# SetResetIC.net
KiCad netlist of a schematic drawn in Altium Designer
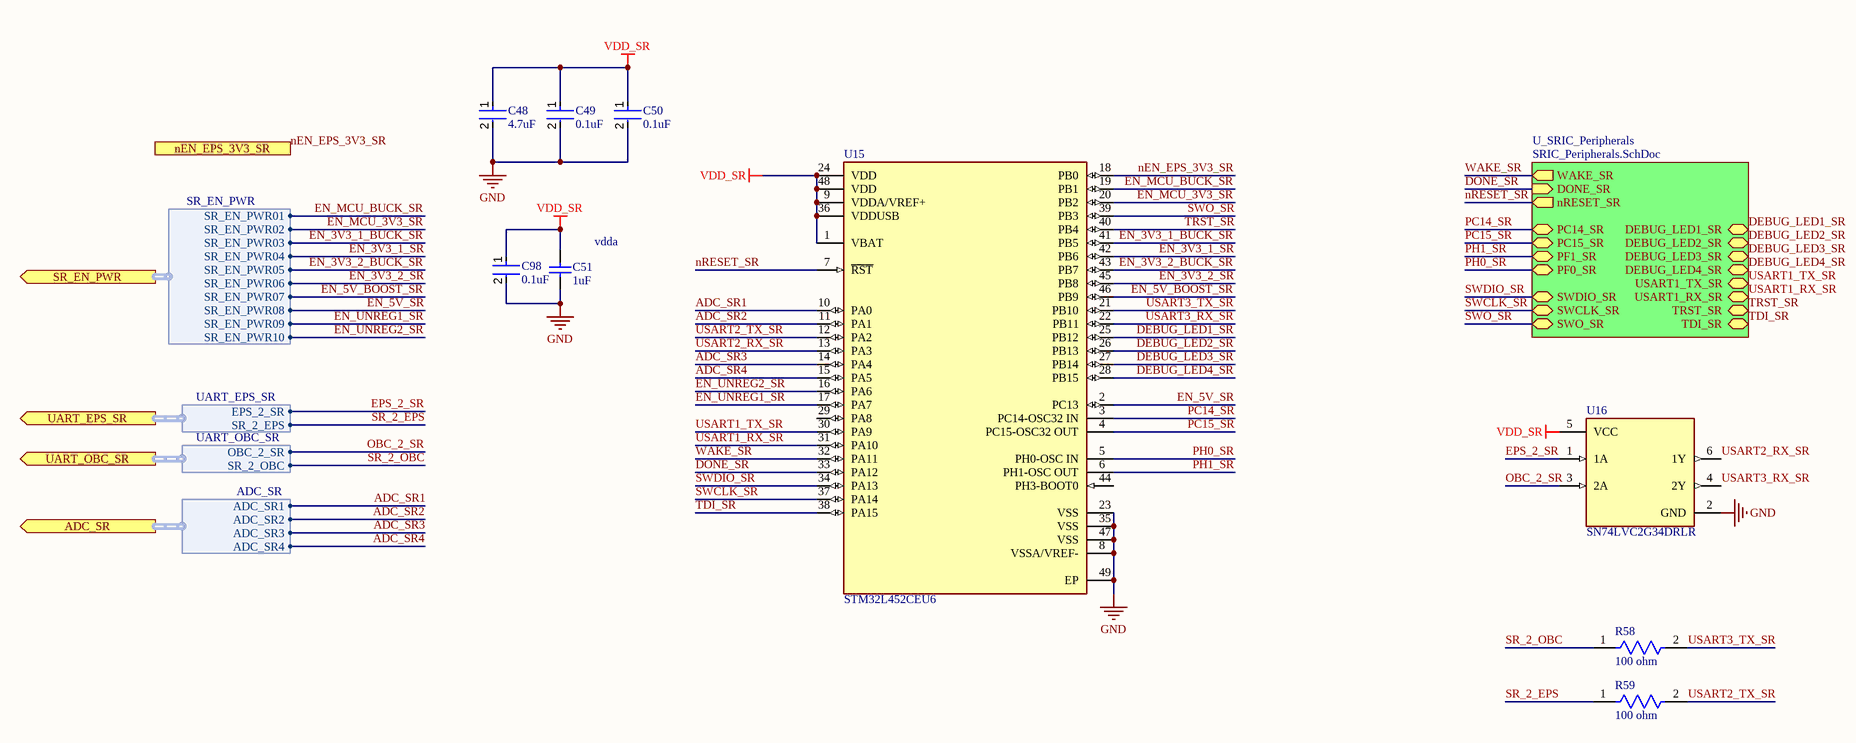
[diagram p0: SetResetIC.SchDoc]

(export (version "E")
  (design (tool "Eeschema 10.0.6"))
  (components
    (comp (ref "C48")
      (value "4.7uF")
      (footprint "FP-GRM188-0_15-IPC_A")
      (description "CAP CER 4.7UF 10V X7S 0603")
      (fields (field (name "TOLERANCE") "10%"))
      (libsource (lib "Altium Content Vault") (part "02cd4be3c70576c341d710602a673aa"))
    )
    (comp (ref "C49")
      (value "0.1uF")
      (footprint "FP-C0603C-CF-MFG")
      (description "CAP CER 0.1UF 50V X7R 0603")
      (fields (field (name "TOLERANCE") "0.1") (field (name "MANUFACTURER") "KEMET"))
      (libsource (lib "Altium Content Vault") (part "b4654b650e69147ec39a6b967a45e02"))
    )
    (comp (ref "C50")
      (value "0.1uF")
      (footprint "FP-C0603C-CF-MFG")
      (description "CAP CER 0.1UF 50V X7R 0603")
      (fields (field (name "TOLERANCE") "0.1") (field (name "MANUFACTURER") "KEMET"))
      (libsource (lib "Altium Content Vault") (part "b4654b650e69147ec39a6b967a45e02"))
    )
    (comp (ref "C51")
      (value "1uF")
      (footprint "CAPC1608X90X35ML10T15")
      (fields (field (name "PART NUMBER") "GRM188R71C105KA12J") (field (name "MANUFACTURER") "Murata"))
      (libsource (lib "Altium Content Vault") (part "CAP"))
    )
    (comp (ref "C98")
      (value "0.1uF")
      (footprint "FP-C0603C-CF-MFG")
      (description "CAP CER 0.1UF 50V X7R 0603")
      (fields (field (name "TOLERANCE") "0.1") (field (name "MANUFACTURER") "KEMET"))
      (libsource (lib "Altium Content Vault") (part "b4654b650e69147ec39a6b967a45e02"))
    )
    (comp (ref "R58")
      (value "100 ohm")
      (footprint "FP-ERJP03-MFG")
      (description "ERJ-P03F1000V SMD Chip Resistor, 100 Ohm, ± 1%, 200 mW, 0603 [1608 Metric], Thick Film, Anti-Surge")
      (fields (field (name "TOLERANCE") "1%"))
      (libsource (lib "Altium Content Vault") (part "1029c3af85768c4190bb7ad29bc67b5"))
    )
    (comp (ref "R59")
      (value "100 ohm")
      (footprint "FP-ERJP03-MFG")
      (description "ERJ-P03F1000V SMD Chip Resistor, 100 Ohm, ± 1%, 200 mW, 0603 [1608 Metric], Thick Film, Anti-Surge")
      (fields (field (name "TOLERANCE") "1%"))
      (libsource (lib "Altium Content Vault") (part "1029c3af85768c4190bb7ad29bc67b5"))
    )
    (comp (ref "U15")
      (value "STM32L452CEU6")
      (footprint "FP-UFQFPN48-A0B9-MFG")
      (description "IC MCU 32BIT 512KB FLASH 48QFPN")
      (libsource (lib "Altium Content Vault") (part "a3bdcff68b454379d220d048bba18d7"))
    )
    (comp (ref "U16")
      (value "SN74LVC2G34DRLR")
      (footprint "FP-DRL0006A-MFG")
      (description "IC BUFFER NON-INVERT 5.5V 6SOT")
      (libsource (lib "Altium Content Vault") (part "59303bce76f5fafbc101ba271662c75"))
    )
  )
  (nets
    (net (code "5") (name "/ADC_SR1") (class "Default")
      (node (ref "U15") (pin "10") (pinfunction "PA0_10") (pintype "bidirectional"))
    )
    (net (code "6") (name "/ADC_SR2") (class "Default")
      (node (ref "U15") (pin "11") (pinfunction "PA1_11") (pintype "bidirectional"))
    )
    (net (code "7") (name "/ADC_SR3") (class "Default")
      (node (ref "U15") (pin "14") (pinfunction "PA4_14") (pintype "bidirectional"))
    )
    (net (code "8") (name "/ADC_SR4") (class "Default")
      (node (ref "U15") (pin "15") (pinfunction "PA5_15") (pintype "bidirectional"))
    )
    (net (code "9") (name "/DEBUG_LED1_SR") (class "Default")
      (node (ref "U15") (pin "25") (pinfunction "PB12_25") (pintype "bidirectional"))
    )
    (net (code "10") (name "/DEBUG_LED2_SR") (class "Default")
      (node (ref "U15") (pin "26") (pinfunction "PB13_26") (pintype "bidirectional"))
    )
    (net (code "11") (name "/DEBUG_LED3_SR") (class "Default")
      (node (ref "U15") (pin "27") (pinfunction "PB14_27") (pintype "bidirectional"))
    )
    (net (code "12") (name "/DEBUG_LED4_SR") (class "Default")
      (node (ref "U15") (pin "28") (pinfunction "PB15_28") (pintype "bidirectional"))
    )
    (net (code "13") (name "/DONE_SR") (class "Default")
      (node (ref "U15") (pin "33") (pinfunction "PA12_33") (pintype "bidirectional"))
    )
    (net (code "14") (name "/EN_3V3_1_BUCK_SR") (class "Default")
      (node (ref "U15") (pin "41") (pinfunction "PB5_41") (pintype "bidirectional"))
    )
    (net (code "15") (name "/EN_3V3_1_SR") (class "Default")
      (node (ref "U15") (pin "42") (pinfunction "PB6_42") (pintype "bidirectional"))
    )
    (net (code "16") (name "/EN_3V3_2_BUCK_SR") (class "Default")
      (node (ref "U15") (pin "43") (pinfunction "PB7_43") (pintype "bidirectional"))
    )
    (net (code "17") (name "/EN_3V3_2_SR") (class "Default")
      (node (ref "U15") (pin "45") (pinfunction "PB8_45") (pintype "bidirectional"))
    )
    (net (code "18") (name "/EN_5V_BOOST_SR") (class "Default")
      (node (ref "U15") (pin "46") (pinfunction "PB9_46") (pintype "bidirectional"))
    )
    (net (code "19") (name "/EN_5V_SR") (class "Default")
      (node (ref "U15") (pin "2") (pinfunction "PC13_2") (pintype "bidirectional"))
    )
    (net (code "20") (name "/EN_MCU_3V3_SR") (class "Default")
      (node (ref "U15") (pin "20") (pinfunction "PB2_20") (pintype "bidirectional"))
    )
    (net (code "21") (name "/EN_MCU_BUCK_SR") (class "Default")
      (node (ref "U15") (pin "19") (pinfunction "PB1_19") (pintype "bidirectional"))
    )
    (net (code "22") (name "/EN_UNREG1_SR") (class "Default")
      (node (ref "U15") (pin "17") (pinfunction "PA7_17") (pintype "bidirectional"))
    )
    (net (code "23") (name "/EN_UNREG2_SR") (class "Default")
      (node (ref "U15") (pin "16") (pinfunction "PA6_16") (pintype "bidirectional"))
    )
    (net (code "24") (name "/EPS_2_SR") (class "Default")
      (node (ref "U16") (pin "1") (pinfunction "1A_1") (pintype "input"))
    )
    (net (code "25") (name "/OBC_2_SR") (class "Default")
      (node (ref "U16") (pin "3") (pinfunction "2A_3") (pintype "input"))
    )
    (net (code "26") (name "/PC14_SR") (class "Default")
      (node (ref "U15") (pin "3") (pinfunction "PC14-OSC32_IN_3") (pintype "passive"))
    )
    (net (code "27") (name "/PC15_SR") (class "Default")
      (node (ref "U15") (pin "4") (pinfunction "PC15-OSC32_OUT_4") (pintype "passive"))
    )
    (net (code "28") (name "/PH0_SR") (class "Default")
      (node (ref "U15") (pin "5") (pinfunction "PH0-OSC_IN_5") (pintype "passive"))
    )
    (net (code "29") (name "/PH1_SR") (class "Default")
      (node (ref "U15") (pin "6") (pinfunction "PH1-OSC_OUT_6") (pintype "passive"))
    )
    (net (code "30") (name "/SR_2_EPS") (class "Default")
      (node (ref "R59") (pin "1") (pinfunction "1_1") (pintype "passive"))
    )
    (net (code "31") (name "/SR_2_OBC") (class "Default")
      (node (ref "R58") (pin "1") (pinfunction "1_1") (pintype "passive"))
    )
    (net (code "32") (name "/SWCLK_SR") (class "Default")
      (node (ref "U15") (pin "37") (pinfunction "PA14_37") (pintype "bidirectional"))
    )
    (net (code "33") (name "/SWDIO_SR") (class "Default")
      (node (ref "U15") (pin "34") (pinfunction "PA13_34") (pintype "bidirectional"))
    )
    (net (code "34") (name "/SWO_SR") (class "Default")
      (node (ref "U15") (pin "39") (pinfunction "PB3_39") (pintype "bidirectional"))
    )
    (net (code "35") (name "/TDI_SR") (class "Default")
      (node (ref "U15") (pin "38") (pinfunction "PA15_38") (pintype "bidirectional"))
    )
    (net (code "36") (name "/TRST_SR") (class "Default")
      (node (ref "U15") (pin "40") (pinfunction "PB4_40") (pintype "bidirectional"))
    )
    (net (code "37") (name "/USART1_RX_SR") (class "Default")
      (node (ref "U15") (pin "31") (pinfunction "PA10_31") (pintype "bidirectional"))
    )
    (net (code "38") (name "/USART1_TX_SR") (class "Default")
      (node (ref "U15") (pin "30") (pinfunction "PA9_30") (pintype "bidirectional"))
    )
    (net (code "39") (name "/USART2_RX_SR") (class "Default")
      (node (ref "U15") (pin "13") (pinfunction "PA3_13") (pintype "bidirectional"))
      (node (ref "U16") (pin "6") (pinfunction "1Y_6") (pintype "output"))
    )
    (net (code "40") (name "/USART2_TX_SR") (class "Default")
      (node (ref "R59") (pin "2") (pinfunction "2_2") (pintype "passive"))
      (node (ref "U15") (pin "12") (pinfunction "PA2_12") (pintype "bidirectional"))
    )
    (net (code "41") (name "/USART3_RX_SR") (class "Default")
      (node (ref "U15") (pin "22") (pinfunction "PB11_22") (pintype "bidirectional"))
      (node (ref "U16") (pin "4") (pinfunction "2Y_4") (pintype "output"))
    )
    (net (code "42") (name "/USART3_TX_SR") (class "Default")
      (node (ref "R58") (pin "2") (pinfunction "2_2") (pintype "passive"))
      (node (ref "U15") (pin "21") (pinfunction "PB10_21") (pintype "bidirectional"))
    )
    (net (code "43") (name "/WAKE_SR") (class "Default")
      (node (ref "U15") (pin "32") (pinfunction "PA11_32") (pintype "bidirectional"))
    )
    (net (code "44") (name "/nEN_EPS_3V3_SR") (class "Default")
      (node (ref "U15") (pin "18") (pinfunction "PB0_18") (pintype "bidirectional"))
    )
    (net (code "45") (name "/nRESET_SR") (class "Default")
      (node (ref "U15") (pin "7") (pinfunction "~{RST}_7") (pintype "input"))
    )
    (net (code "50") (name "GND") (class "Default")
      (node (ref "C48") (pin "2") (pinfunction "2_2") (pintype "passive"))
      (node (ref "C49") (pin "2") (pinfunction "2_2") (pintype "passive"))
      (node (ref "C50") (pin "2") (pinfunction "2_2") (pintype "passive"))
      (node (ref "C51") (pin "1") (pinfunction "1_1") (pintype "passive"))
      (node (ref "C98") (pin "2") (pinfunction "2_2") (pintype "passive"))
      (node (ref "U15") (pin "23") (pinfunction "VSS_23") (pintype "power_in"))
      (node (ref "U15") (pin "35") (pinfunction "VSS_35") (pintype "power_in"))
      (node (ref "U15") (pin "47") (pinfunction "VSS_47") (pintype "power_in"))
      (node (ref "U15") (pin "49") (pinfunction "EP_49") (pintype "power_in"))
      (node (ref "U15") (pin "8") (pinfunction "VSSA/VREF-_8") (pintype "power_in"))
      (node (ref "U16") (pin "2") (pinfunction "GND_2") (pintype "power_in"))
    )
    (net (code "51") (name "VDD_SR") (class "Default")
      (node (ref "C48") (pin "1") (pinfunction "1_1") (pintype "passive"))
      (node (ref "C49") (pin "1") (pinfunction "1_1") (pintype "passive"))
      (node (ref "C50") (pin "1") (pinfunction "1_1") (pintype "passive"))
      (node (ref "C51") (pin "2") (pinfunction "2_2") (pintype "passive"))
      (node (ref "C98") (pin "1") (pinfunction "1_1") (pintype "passive"))
      (node (ref "U15") (pin "1") (pinfunction "VBAT_1") (pintype "power_in"))
      (node (ref "U15") (pin "24") (pinfunction "VDD_24") (pintype "power_in"))
      (node (ref "U15") (pin "36") (pinfunction "VDDUSB_36") (pintype "power_in"))
      (node (ref "U15") (pin "48") (pinfunction "VDD_48") (pintype "power_in"))
      (node (ref "U15") (pin "9") (pinfunction "VDDA/VREF+_9") (pintype "power_in"))
      (node (ref "U16") (pin "5") (pinfunction "VCC_5") (pintype "power_in"))
    )
    (net (code "52") (name "unconnected-(U15-PA8-Pad29)") (class "Default")
      (node (ref "U15") (pin "29") (pinfunction "PA8_29") (pintype "bidirectional"))
    )
    (net (code "53") (name "unconnected-(U15-PH3-BOOT0-Pad44)") (class "Default")
      (node (ref "U15") (pin "44") (pinfunction "PH3-BOOT0_44") (pintype "input"))
    )
  )
)
